# Energy_SensorRevB.net
KiCad netlist of a schematic drawn in EAGLE
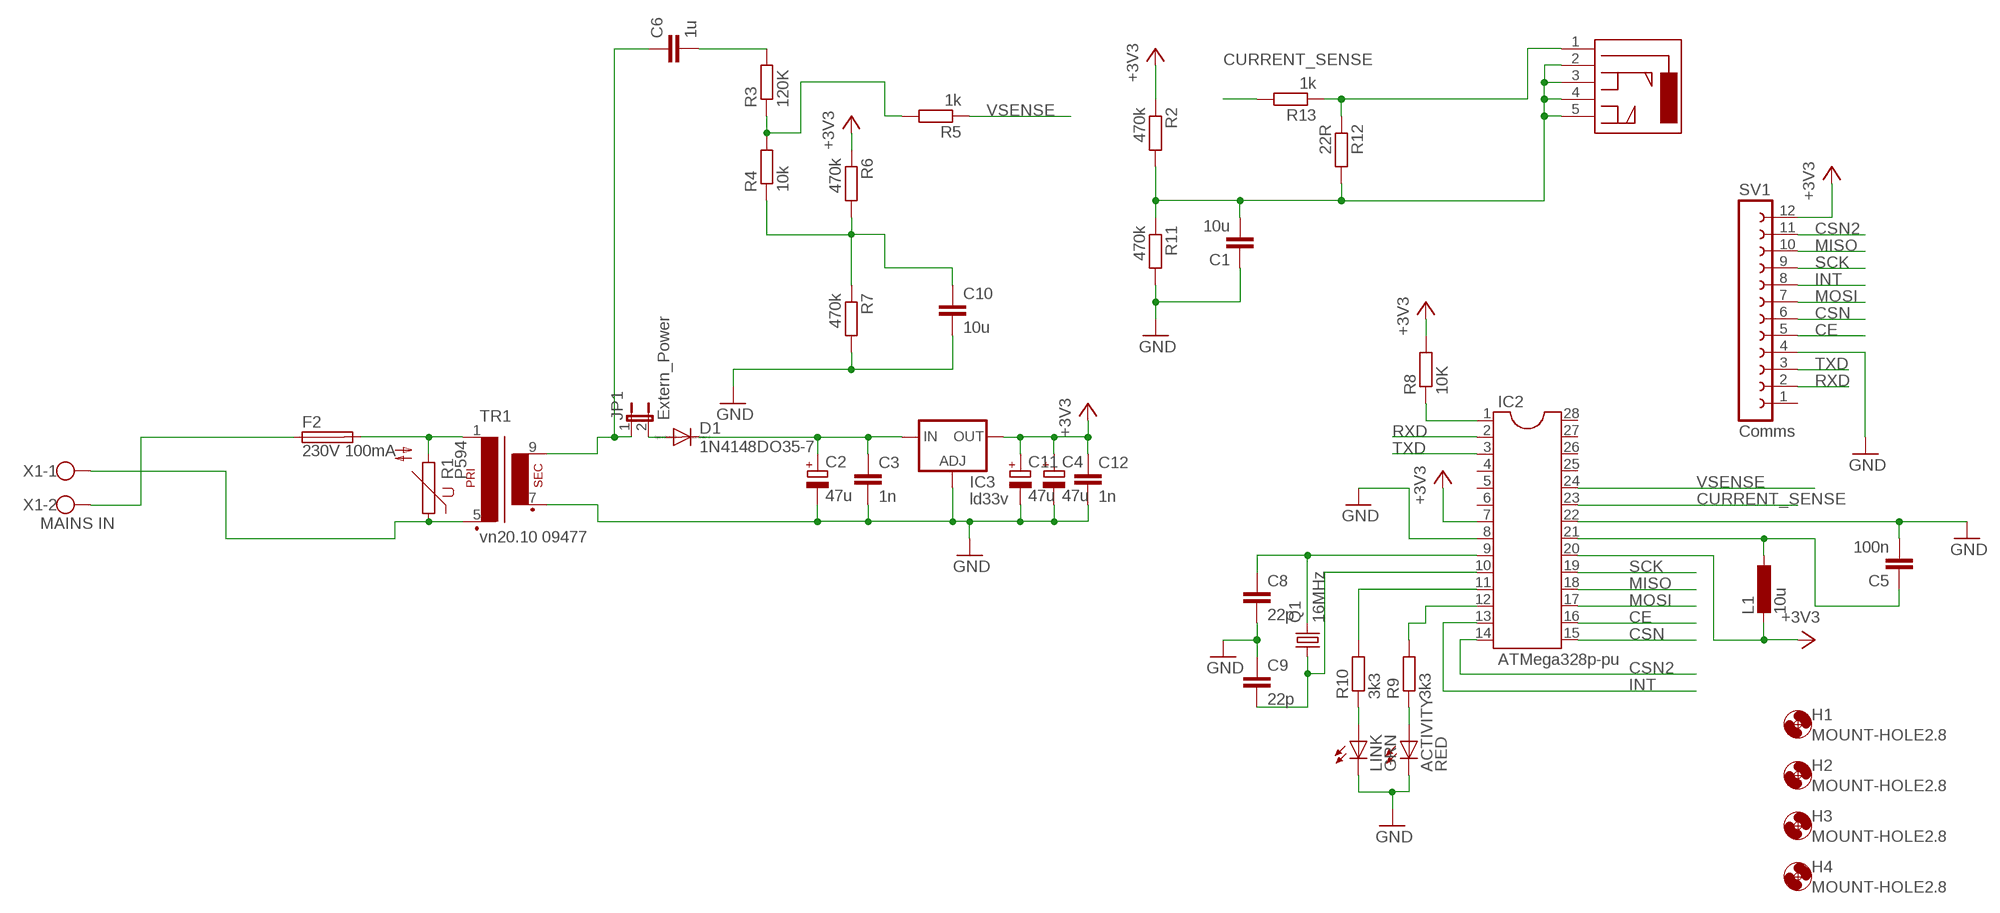
[diagram p0: schematic, sheet 1]

(export (version "E")
  (design (tool "Eeschema 10.0.6"))
  (components
    (comp (ref "ACTIVITY")
      (value "RED")
      (footprint "eagle-import:LED5MM")
      (libsource (lib "eagle-import") (part "LED5MM"))
    )
    (comp (ref "C1")
      (value "10u")
      (footprint "eagle-import:C1206K")
      (libsource (lib "eagle-import") (part "C-EUC1206K"))
    )
    (comp (ref "C2")
      (value "47u")
      (footprint "eagle-import:E3,5-10")
      (libsource (lib "eagle-import") (part "CPOL-EUE3.5-10"))
    )
    (comp (ref "C3")
      (value "1n")
      (footprint "eagle-import:C025-025X050")
      (libsource (lib "eagle-import") (part "C-EU025-025X050"))
    )
    (comp (ref "C4")
      (value "47u")
      (footprint "eagle-import:E3,5-8")
      (libsource (lib "eagle-import") (part "CPOL-EUE3.5-8"))
    )
    (comp (ref "C5")
      (value "100n")
      (footprint "eagle-import:C1206K")
      (libsource (lib "eagle-import") (part "C-EUC1206K"))
    )
    (comp (ref "C6")
      (value "1u")
      (footprint "eagle-import:C1206K")
      (libsource (lib "eagle-import") (part "C-EUC1206K"))
    )
    (comp (ref "C8")
      (value "22p")
      (footprint "eagle-import:C025-025X050")
      (libsource (lib "eagle-import") (part "C-EU025-025X050"))
    )
    (comp (ref "C9")
      (value "22p")
      (footprint "eagle-import:C025-025X050")
      (libsource (lib "eagle-import") (part "C-EU025-025X050"))
    )
    (comp (ref "C10")
      (value "10u")
      (footprint "eagle-import:C1206K")
      (libsource (lib "eagle-import") (part "C-EUC1206K"))
    )
    (comp (ref "C11")
      (value "47u")
      (footprint "eagle-import:E3,5-8")
      (libsource (lib "eagle-import") (part "CPOL-EUE3.5-8"))
    )
    (comp (ref "C12")
      (value "1n")
      (footprint "eagle-import:C025-025X050")
      (libsource (lib "eagle-import") (part "C-EU025-025X050"))
    )
    (comp (ref "D1")
      (value "1N4148DO35-7")
      (footprint "eagle-import:DO35-7")
      (libsource (lib "eagle-import") (part "1N4148DO35-7"))
    )
    (comp (ref "F2")
      (value "230V 100mA")
      (footprint "eagle-import:SH22,5A")
      (fields (field (name "MPN") "0031.7701.11"))
      (libsource (lib "eagle-import") (part "SH22,5A"))
    )
    (comp (ref "H1")
      (value "MOUNT-HOLE2.8")
      (footprint "eagle-import:2,8")
      (libsource (lib "eagle-import") (part "MOUNT-HOLE2.8"))
    )
    (comp (ref "H2")
      (value "MOUNT-HOLE2.8")
      (footprint "eagle-import:2,8")
      (libsource (lib "eagle-import") (part "MOUNT-HOLE2.8"))
    )
    (comp (ref "H3")
      (value "MOUNT-HOLE2.8")
      (footprint "eagle-import:2,8")
      (libsource (lib "eagle-import") (part "MOUNT-HOLE2.8"))
    )
    (comp (ref "H4")
      (value "MOUNT-HOLE2.8")
      (footprint "eagle-import:2,8")
      (libsource (lib "eagle-import") (part "MOUNT-HOLE2.8"))
    )
    (comp (ref "IC2")
      (value "ATMega328p-pu")
      (footprint "eagle-import:DIL28-3")
      (libsource (lib "eagle-import") (part "DIL28-3"))
    )
    (comp (ref "IC3")
      (value "ld33v")
      (footprint "eagle-import:317TL")
      (libsource (lib "eagle-import") (part "LM317TL"))
    )
    (comp (ref "JP1")
      (value "Extern_Power")
      (footprint "eagle-import:JP1")
      (libsource (lib "eagle-import") (part "JP1E"))
    )
    (comp (ref "L1")
      (value "10u")
      (footprint "eagle-import:L3230M")
      (libsource (lib "eagle-import") (part "L-EUL3230M"))
    )
    (comp (ref "LINK")
      (value "GRN")
      (footprint "eagle-import:LED5MM")
      (libsource (lib "eagle-import") (part "LED5MM"))
    )
    (comp (ref "Q1")
      (value "16MHz")
      (footprint "eagle-import:HC49_S")
      (libsource (lib "eagle-import") (part "CRYSTALHC49S"))
    )
    (comp (ref "R1")
      (value "P594")
      (footprint "eagle-import:P594")
      (libsource (lib "eagle-import") (part "P594"))
    )
    (comp (ref "R2")
      (value "470k")
      (footprint "eagle-import:0207_7")
      (libsource (lib "eagle-import") (part "R-EU_0207/7"))
    )
    (comp (ref "R3")
      (value "120K")
      (footprint "eagle-import:0207_7")
      (libsource (lib "eagle-import") (part "R-EU_0207/7"))
    )
    (comp (ref "R4")
      (value "10k")
      (footprint "eagle-import:R1206")
      (libsource (lib "eagle-import") (part "R-EU_R1206"))
    )
    (comp (ref "R5")
      (value "1k")
      (footprint "eagle-import:0207_7")
      (libsource (lib "eagle-import") (part "R-EU_0207/7"))
    )
    (comp (ref "R6")
      (value "470k")
      (footprint "eagle-import:0207_7")
      (libsource (lib "eagle-import") (part "R-EU_0207/7"))
    )
    (comp (ref "R7")
      (value "470k")
      (footprint "eagle-import:0207_7")
      (libsource (lib "eagle-import") (part "R-EU_0207/7"))
    )
    (comp (ref "R8")
      (value "10K")
      (footprint "eagle-import:0207_7")
      (libsource (lib "eagle-import") (part "R-EU_0207/7"))
    )
    (comp (ref "R9")
      (value "3k3")
      (footprint "eagle-import:0207_7")
      (libsource (lib "eagle-import") (part "R-EU_0207/7"))
    )
    (comp (ref "R10")
      (value "3k3")
      (footprint "eagle-import:0207_7")
      (libsource (lib "eagle-import") (part "R-EU_0207/7"))
    )
    (comp (ref "R11")
      (value "470k")
      (footprint "eagle-import:0207_7")
      (libsource (lib "eagle-import") (part "R-EU_0207/7"))
    )
    (comp (ref "R12")
      (value "22R")
      (footprint "eagle-import:R1206")
      (libsource (lib "eagle-import") (part "R-EU_R1206"))
    )
    (comp (ref "R13")
      (value "1k")
      (footprint "eagle-import:0207_7")
      (libsource (lib "eagle-import") (part "R-EU_0207/7"))
    )
    (comp (ref "SV1")
      (value "Comms")
      (footprint "eagle-import:FE12W")
      (libsource (lib "eagle-import") (part "FE12W"))
    )
    (comp (ref "TR1")
      (value "vn20.10 09477")
      (footprint "eagle-import:VV11")
      (libsource (lib "eagle-import") (part "VV11"))
    )
    (comp (ref "U$1")
      (value "3.5MMJACK")
      (footprint "eagle-import:3.5MMJACK")
      (libsource (lib "eagle-import") (part "3.5MMJACK"))
    )
    (comp (ref "X1")
      (value "MAINS IN")
      (footprint "eagle-import:W237-102")
      (fields (field (name "MPN") "237-102"))
      (libsource (lib "eagle-import") (part "W237-102"))
    )
  )
  (nets
    (net (code "1") (name "+3V3") (class "Default")
      (node (ref "C11") (pin "+") (pinfunction "+_+") (pintype "passive"))
      (node (ref "C12") (pin "1") (pinfunction "1_1") (pintype "passive"))
      (node (ref "C4") (pin "+") (pinfunction "+_+") (pintype "passive"))
      (node (ref "IC2") (pin "20") (pinfunction "20_20") (pintype "passive"))
      (node (ref "IC2") (pin "7") (pinfunction "7_7") (pintype "passive"))
      (node (ref "IC3") (pin "2") (pinfunction "OUT_2") (pintype "passive"))
      (node (ref "L1") (pin "2") (pinfunction "2_2") (pintype "passive"))
      (node (ref "R2") (pin "1") (pinfunction "1_1") (pintype "passive"))
      (node (ref "R6") (pin "1") (pinfunction "1_1") (pintype "passive"))
      (node (ref "R8") (pin "2") (pinfunction "2_2") (pintype "passive"))
      (node (ref "SV1") (pin "12") (pinfunction "12_12") (pintype "passive"))
    )
    (net (code "2") (name "/CE") (class "Default")
      (node (ref "IC2") (pin "16") (pinfunction "16_16") (pintype "passive"))
      (node (ref "SV1") (pin "5") (pinfunction "5_5") (pintype "passive"))
    )
    (net (code "3") (name "/CSN") (class "Default")
      (node (ref "IC2") (pin "15") (pinfunction "15_15") (pintype "passive"))
      (node (ref "SV1") (pin "6") (pinfunction "6_6") (pintype "passive"))
    )
    (net (code "4") (name "/CSN2") (class "Default")
      (node (ref "IC2") (pin "14") (pinfunction "14_14") (pintype "passive"))
      (node (ref "SV1") (pin "11") (pinfunction "11_11") (pintype "passive"))
    )
    (net (code "5") (name "/CURRENT_SENSE") (class "Default")
      (node (ref "IC2") (pin "23") (pinfunction "23_23") (pintype "passive"))
      (node (ref "R13") (pin "2") (pinfunction "2_2") (pintype "passive"))
    )
    (net (code "6") (name "/INT") (class "Default")
      (node (ref "IC2") (pin "13") (pinfunction "13_13") (pintype "passive"))
      (node (ref "SV1") (pin "8") (pinfunction "8_8") (pintype "passive"))
    )
    (net (code "7") (name "/MISO") (class "Default")
      (node (ref "IC2") (pin "18") (pinfunction "18_18") (pintype "passive"))
      (node (ref "SV1") (pin "10") (pinfunction "10_10") (pintype "passive"))
    )
    (net (code "8") (name "/MOSI") (class "Default")
      (node (ref "IC2") (pin "17") (pinfunction "17_17") (pintype "passive"))
      (node (ref "SV1") (pin "7") (pinfunction "7_7") (pintype "passive"))
    )
    (net (code "9") (name "/RXD") (class "Default")
      (node (ref "IC2") (pin "2") (pinfunction "2_2") (pintype "passive"))
      (node (ref "SV1") (pin "2") (pinfunction "2_2") (pintype "passive"))
    )
    (net (code "10") (name "/SCK") (class "Default")
      (node (ref "IC2") (pin "19") (pinfunction "19_19") (pintype "passive"))
      (node (ref "SV1") (pin "9") (pinfunction "9_9") (pintype "passive"))
    )
    (net (code "11") (name "/TXD") (class "Default")
      (node (ref "IC2") (pin "3") (pinfunction "3_3") (pintype "passive"))
      (node (ref "SV1") (pin "3") (pinfunction "3_3") (pintype "passive"))
    )
    (net (code "12") (name "/VSENSE") (class "Default")
      (node (ref "IC2") (pin "24") (pinfunction "24_24") (pintype "passive"))
      (node (ref "R5") (pin "1") (pinfunction "1_1") (pintype "passive"))
    )
    (net (code "13") (name "GND") (class "Default")
      (node (ref "ACTIVITY") (pin "K") (pinfunction "C_K") (pintype "passive"))
      (node (ref "C1") (pin "1") (pinfunction "1_1") (pintype "passive"))
      (node (ref "C10") (pin "2") (pinfunction "2_2") (pintype "passive"))
      (node (ref "C11") (pin "-") (pinfunction "-_-") (pintype "passive"))
      (node (ref "C12") (pin "2") (pinfunction "2_2") (pintype "passive"))
      (node (ref "C2") (pin "-") (pinfunction "-_-") (pintype "passive"))
      (node (ref "C3") (pin "2") (pinfunction "2_2") (pintype "passive"))
      (node (ref "C4") (pin "-") (pinfunction "-_-") (pintype "passive"))
      (node (ref "C5") (pin "2") (pinfunction "2_2") (pintype "passive"))
      (node (ref "C8") (pin "2") (pinfunction "2_2") (pintype "passive"))
      (node (ref "C9") (pin "1") (pinfunction "1_1") (pintype "passive"))
      (node (ref "IC2") (pin "22") (pinfunction "22_22") (pintype "passive"))
      (node (ref "IC2") (pin "8") (pinfunction "8_8") (pintype "passive"))
      (node (ref "IC3") (pin "1") (pinfunction "ADJ_1") (pintype "input"))
      (node (ref "LINK") (pin "K") (pinfunction "C_K") (pintype "passive"))
      (node (ref "R11") (pin "2") (pinfunction "2_2") (pintype "passive"))
      (node (ref "R7") (pin "2") (pinfunction "2_2") (pintype "passive"))
      (node (ref "SV1") (pin "4") (pinfunction "4_4") (pintype "passive"))
      (node (ref "TR1") (pin "7") (pinfunction "S3_7") (pintype "passive"))
    )
    (net (code "14") (name "Net-(ACTIVITY-PadA)") (class "Default")
      (node (ref "ACTIVITY") (pin "A") (pinfunction "A_A") (pintype "passive"))
      (node (ref "R9") (pin "1") (pinfunction "1_1") (pintype "passive"))
    )
    (net (code "15") (name "Net-(C5-Pad1)") (class "Default")
      (node (ref "C5") (pin "1") (pinfunction "1_1") (pintype "passive"))
      (node (ref "IC2") (pin "21") (pinfunction "21_21") (pintype "passive"))
      (node (ref "L1") (pin "1") (pinfunction "1_1") (pintype "passive"))
    )
    (net (code "16") (name "Net-(C6-Pad2)") (class "Default")
      (node (ref "C6") (pin "2") (pinfunction "2_2") (pintype "passive"))
      (node (ref "R3") (pin "2") (pinfunction "2_2") (pintype "passive"))
    )
    (net (code "17") (name "Net-(C8-Pad1)") (class "Default")
      (node (ref "C8") (pin "1") (pinfunction "1_1") (pintype "passive"))
      (node (ref "IC2") (pin "9") (pinfunction "9_9") (pintype "passive"))
      (node (ref "Q1") (pin "2") (pinfunction "2_2") (pintype "passive"))
    )
    (net (code "18") (name "Net-(C9-Pad2)") (class "Default")
      (node (ref "C9") (pin "2") (pinfunction "2_2") (pintype "passive"))
      (node (ref "IC2") (pin "10") (pinfunction "10_10") (pintype "passive"))
      (node (ref "Q1") (pin "1") (pinfunction "1_1") (pintype "passive"))
    )
    (net (code "19") (name "Net-(C10-Pad1)") (class "Default")
      (node (ref "C10") (pin "1") (pinfunction "1_1") (pintype "passive"))
      (node (ref "R4") (pin "1") (pinfunction "1_1") (pintype "passive"))
      (node (ref "R6") (pin "2") (pinfunction "2_2") (pintype "passive"))
      (node (ref "R7") (pin "1") (pinfunction "1_1") (pintype "passive"))
    )
    (net (code "20") (name "Net-(D1-PadA)") (class "Default")
      (node (ref "D1") (pin "A") (pinfunction "A_A") (pintype "passive"))
      (node (ref "JP1") (pin "2") (pinfunction "2_2") (pintype "passive"))
    )
    (net (code "21") (name "Net-(IC2-Pad1)") (class "Default")
      (node (ref "IC2") (pin "1") (pinfunction "1_1") (pintype "passive"))
      (node (ref "R8") (pin "1") (pinfunction "1_1") (pintype "passive"))
    )
    (net (code "22") (name "Net-(IC2-Pad11)") (class "Default")
      (node (ref "IC2") (pin "11") (pinfunction "11_11") (pintype "passive"))
      (node (ref "R10") (pin "2") (pinfunction "2_2") (pintype "passive"))
    )
    (net (code "23") (name "Net-(IC2-Pad12)") (class "Default")
      (node (ref "IC2") (pin "12") (pinfunction "12_12") (pintype "passive"))
      (node (ref "R9") (pin "2") (pinfunction "2_2") (pintype "passive"))
    )
    (net (code "24") (name "Net-(IC3-IN)") (class "Default")
      (node (ref "C2") (pin "+") (pinfunction "+_+") (pintype "passive"))
      (node (ref "C3") (pin "1") (pinfunction "1_1") (pintype "passive"))
      (node (ref "D1") (pin "C") (pinfunction "C_C") (pintype "passive"))
      (node (ref "IC3") (pin "3") (pinfunction "IN_3") (pintype "input"))
    )
    (net (code "25") (name "Net-(LINK-PadA)") (class "Default")
      (node (ref "LINK") (pin "A") (pinfunction "A_A") (pintype "passive"))
      (node (ref "R10") (pin "1") (pinfunction "1_1") (pintype "passive"))
    )
    (net (code "26") (name "Net-(R3-Pad1)") (class "Default")
      (node (ref "R3") (pin "1") (pinfunction "1_1") (pintype "passive"))
      (node (ref "R4") (pin "2") (pinfunction "2_2") (pintype "passive"))
      (node (ref "R5") (pin "2") (pinfunction "2_2") (pintype "passive"))
    )
    (net (code "27") (name "Net-(TR1-P1)") (class "Default")
      (node (ref "F2") (pin "2") (pinfunction "2_2") (pintype "passive"))
      (node (ref "R1") (pin "2") (pinfunction "2_2") (pintype "passive"))
      (node (ref "TR1") (pin "1") (pinfunction "P1_1") (pintype "passive"))
    )
    (net (code "28") (name "Net-(TR1-P2)") (class "Default")
      (node (ref "R1") (pin "1") (pinfunction "1_1") (pintype "passive"))
      (node (ref "TR1") (pin "5") (pinfunction "P2_5") (pintype "passive"))
      (node (ref "X1") (pin "1") (pinfunction "KL_1") (pintype "passive"))
    )
    (net (code "29") (name "Net-(TR1-S4)") (class "Default")
      (node (ref "C6") (pin "1") (pinfunction "1_1") (pintype "passive"))
      (node (ref "JP1") (pin "1") (pinfunction "1_1") (pintype "passive"))
      (node (ref "TR1") (pin "9") (pinfunction "S4_9") (pintype "passive"))
    )
    (net (code "30") (name "Net-(U$1-P$1)") (class "Default")
      (node (ref "R12") (pin "1") (pinfunction "1_1") (pintype "passive"))
      (node (ref "R13") (pin "1") (pinfunction "1_1") (pintype "passive"))
      (node (ref "U$1") (pin "1") (pinfunction "P$1_1") (pintype "bidirectional"))
    )
    (net (code "31") (name "Net-(U$1-P$2)") (class "Default")
      (node (ref "C1") (pin "2") (pinfunction "2_2") (pintype "passive"))
      (node (ref "R11") (pin "1") (pinfunction "1_1") (pintype "passive"))
      (node (ref "R12") (pin "2") (pinfunction "2_2") (pintype "passive"))
      (node (ref "R2") (pin "2") (pinfunction "2_2") (pintype "passive"))
      (node (ref "U$1") (pin "2") (pinfunction "P$2_2") (pintype "bidirectional"))
      (node (ref "U$1") (pin "3") (pinfunction "P$3_3") (pintype "bidirectional"))
      (node (ref "U$1") (pin "4") (pinfunction "P$4_4") (pintype "bidirectional"))
      (node (ref "U$1") (pin "5") (pinfunction "P$5_5") (pintype "bidirectional"))
    )
    (net (code "32") (name "Net-(X1B-KL)") (class "Default")
      (node (ref "F2") (pin "1") (pinfunction "1_1") (pintype "passive"))
      (node (ref "X1") (pin "2") (pinfunction "KL_2") (pintype "passive"))
    )
    (net (code "33") (name "unconnected-(IC2-Pad4)") (class "Default")
      (node (ref "IC2") (pin "4") (pinfunction "4_4") (pintype "passive"))
    )
    (net (code "34") (name "unconnected-(IC2-Pad5)") (class "Default")
      (node (ref "IC2") (pin "5") (pinfunction "5_5") (pintype "passive"))
    )
    (net (code "35") (name "unconnected-(IC2-Pad6)") (class "Default")
      (node (ref "IC2") (pin "6") (pinfunction "6_6") (pintype "passive"))
    )
    (net (code "36") (name "unconnected-(IC2-Pad25)") (class "Default")
      (node (ref "IC2") (pin "25") (pinfunction "25_25") (pintype "passive"))
    )
    (net (code "37") (name "unconnected-(IC2-Pad26)") (class "Default")
      (node (ref "IC2") (pin "26") (pinfunction "26_26") (pintype "passive"))
    )
    (net (code "38") (name "unconnected-(IC2-Pad27)") (class "Default")
      (node (ref "IC2") (pin "27") (pinfunction "27_27") (pintype "passive"))
    )
    (net (code "39") (name "unconnected-(IC2-Pad28)") (class "Default")
      (node (ref "IC2") (pin "28") (pinfunction "28_28") (pintype "passive"))
    )
    (net (code "40") (name "unconnected-(SV1-Pad1)") (class "Default")
      (node (ref "SV1") (pin "1") (pinfunction "1_1") (pintype "passive"))
    )
  )
)
